# msp430g2553o.net
KiCad netlist of a schematic drawn in Altium Designer
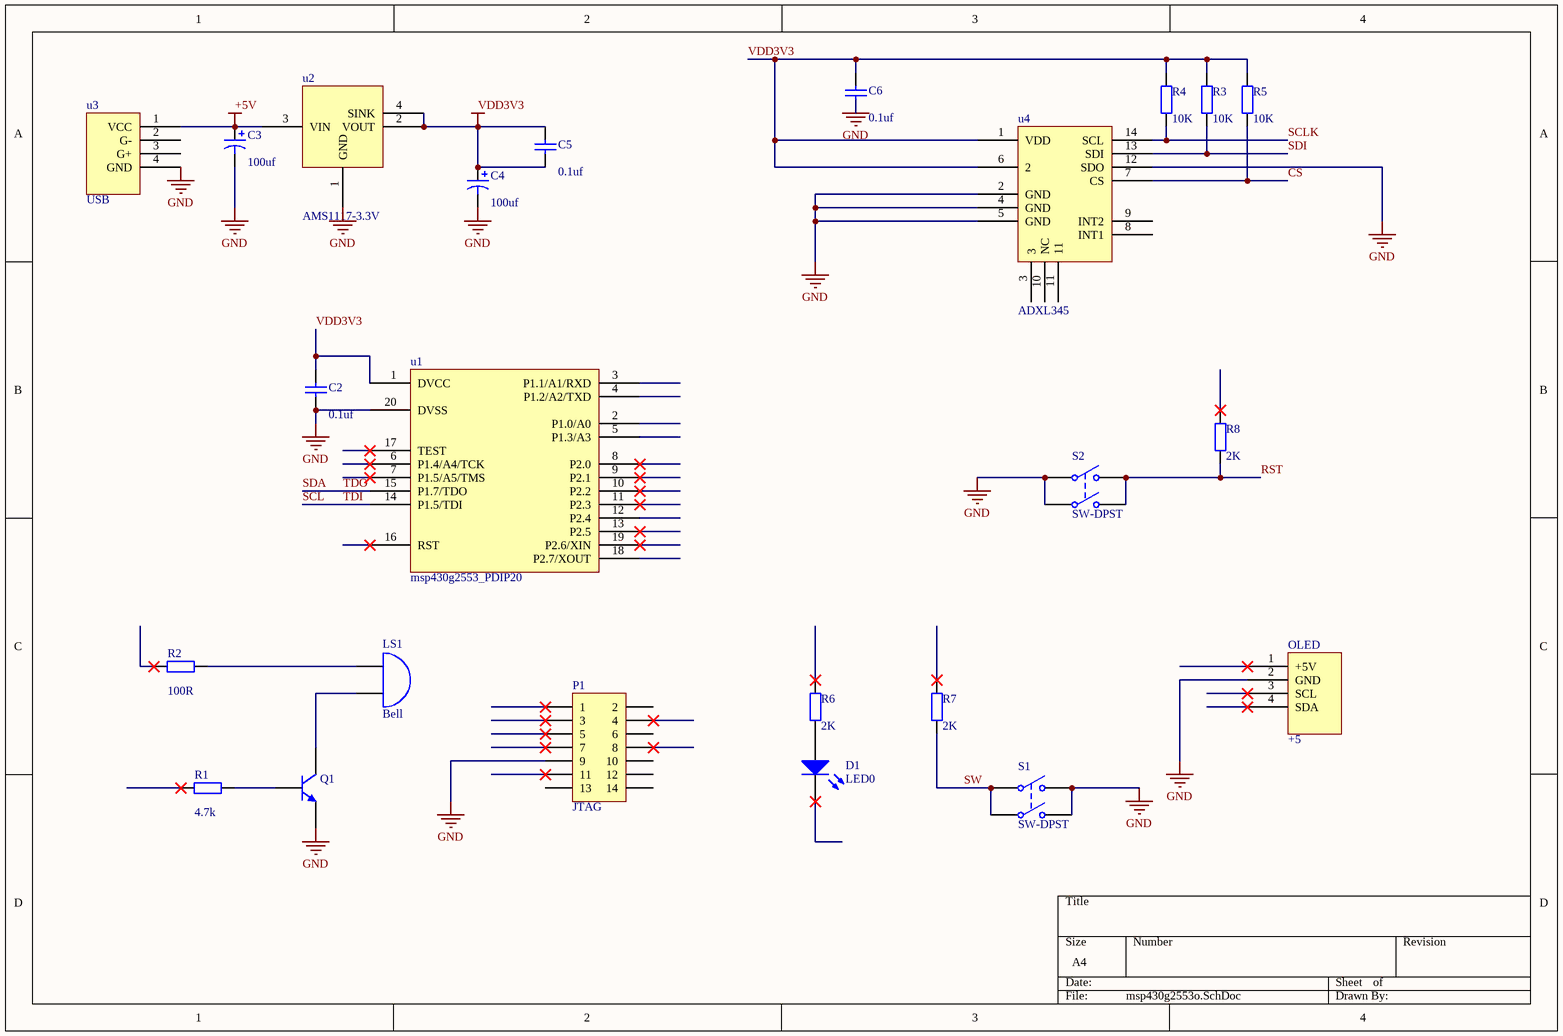
[diagram p0: msp430g2553o.SchDoc]

(export (version "E")
  (design (tool "Eeschema 10.0.6"))
  (components
    (comp (ref "C2")
      (value "0.1uf")
      (footprint "6-0805_N")
      (description "Capacitor")
      (fields (field (name "Comment") "Cap") (field (name "PUBLISHER") "Altium Limited"))
      (libsource (lib "msp430g2553") (part "Cap"))
    )
    (comp (ref "C3")
      (value "100uf")
      (footprint "Cap2_polar")
      (description "Polarized Capacitor (Axial)")
      (fields (field (name "Comment") "Cap Pol2") (field (name "PUBLISHER") "Altium Limited"))
      (libsource (lib "msp430g2553") (part "Cap Pol2"))
    )
    (comp (ref "C4")
      (value "100uf")
      (footprint "Cap2_polar")
      (description "Polarized Capacitor (Axial)")
      (fields (field (name "Comment") "Cap Pol2") (field (name "PUBLISHER") "Altium Limited"))
      (libsource (lib "msp430g2553") (part "Cap Pol2"))
    )
    (comp (ref "C5")
      (value "0.1uf")
      (footprint "6-0805_N")
      (description "Capacitor")
      (fields (field (name "Comment") "Cap") (field (name "PUBLISHER") "Altium Limited"))
      (libsource (lib "msp430g2553") (part "Cap"))
    )
    (comp (ref "C6")
      (value "0.1uf")
      (footprint "6-0805_N")
      (description "Capacitor")
      (fields (field (name "Comment") "Cap") (field (name "PUBLISHER") "Altium Limited"))
      (libsource (lib "msp430g2553") (part "Cap"))
    )
    (comp (ref "D1")
      (value "LED0")
      (footprint "6-0805_N - duplicate")
      (description "Typical INFRARED GaAs LED")
      (fields (field (name "PUBLISHER") "Altium Limited"))
      (libsource (lib "msp430g2553") (part "LED0"))
    )
    (comp (ref "LS1")
      (value "Bell")
      (footprint "bell")
      (description "Electrical Bell")
      (fields (field (name "PUBLISHER") "Altium Limited"))
      (libsource (lib "msp430g2553") (part "Bell"))
    )
    (comp (ref "OLED") (value "+5") (footprint "OLED") (libsource (lib "msp430g2553") (part "OLED")))
    (comp (ref "P1")
      (value "JTAG")
      (footprint "HDR2X7H")
      (description "Header, 7-Pin, Dual row")
      (fields (field (name "PUBLISHER") "Altium Limited"))
      (libsource (lib "msp430g2553") (part "JTAG"))
    )
    (comp (ref "Q1")
      (value "NPN")
      (footprint "SOT23_N")
      (description "NPN Bipolar Transistor")
      (fields (field (name "PUBLISHER") "Altium Limited"))
      (libsource (lib "msp430g2553") (part "NPN"))
    )
    (comp (ref "R1")
      (value "4.7k")
      (footprint "6-0805_N")
      (description "Resistor")
      (fields (field (name "Comment") "Res2") (field (name "PUBLISHER") "Altium Limited"))
      (libsource (lib "") (part "Res2_1"))
    )
    (comp (ref "R2")
      (value "100R")
      (footprint "6-0805_N")
      (description "Resistor")
      (fields (field (name "Comment") "Res2") (field (name "PUBLISHER") "Altium Limited"))
      (libsource (lib "") (part "Res2_1"))
    )
    (comp (ref "R3")
      (value "10K")
      (footprint "6-0805_N")
      (description "Resistor")
      (fields (field (name "Comment") "Res2") (field (name "PUBLISHER") "Altium Limited"))
      (libsource (lib "msp430g2553") (part "Res2"))
    )
    (comp (ref "R4")
      (value "10K")
      (footprint "6-0805_N")
      (description "Resistor")
      (fields (field (name "Comment") "Res2") (field (name "PUBLISHER") "Altium Limited"))
      (libsource (lib "msp430g2553") (part "Res2"))
    )
    (comp (ref "R5")
      (value "10K")
      (footprint "6-0805_N")
      (description "Resistor")
      (fields (field (name "Comment") "Res2") (field (name "PUBLISHER") "Altium Limited"))
      (libsource (lib "msp430g2553") (part "Res2"))
    )
    (comp (ref "R6")
      (value "2K")
      (footprint "6-0805_N")
      (description "Resistor")
      (fields (field (name "Comment") "Res2") (field (name "PUBLISHER") "Altium Limited"))
      (libsource (lib "msp430g2553") (part "Res2"))
    )
    (comp (ref "R7")
      (value "2K")
      (footprint "6-0805_N")
      (description "Resistor")
      (fields (field (name "Comment") "Res2") (field (name "PUBLISHER") "Altium Limited"))
      (libsource (lib "msp430g2553") (part "Res2"))
    )
    (comp (ref "R8")
      (value "2K")
      (footprint "6-0805_N")
      (description "Resistor")
      (fields (field (name "Comment") "Res2") (field (name "PUBLISHER") "Altium Limited"))
      (libsource (lib "msp430g2553") (part "Res2"))
    )
    (comp (ref "S1")
      (value "SW-DPST")
      (footprint "DPST-4")
      (description "Double-Pole, Single-Throw Switch")
      (fields (field (name "PUBLISHER") "Altium Limited"))
      (libsource (lib "msp430g2553") (part "SW-DPST"))
    )
    (comp (ref "S2")
      (value "SW-DPST")
      (footprint "DPST-4")
      (description "Double-Pole, Single-Throw Switch")
      (fields (field (name "PUBLISHER") "Altium Limited"))
      (libsource (lib "msp430g2553") (part "SW-DPST"))
    )
    (comp (ref "u1")
      (value "msp430g2553_PDIP20")
      (footprint "DIP20")
      (libsource (lib "msp430g2553") (part "msp430g2553_PDIP20"))
    )
    (comp (ref "u2")
      (value "AMS1117-3.3V")
      (footprint "SOT223_N")
      (libsource (lib "msp430g2553") (part "AMS1117-3.3V"))
    )
    (comp (ref "u3") (value "USB") (footprint "USB2.5-2H4") (libsource (lib "msp430g2553") (part "USB")))
    (comp (ref "u4") (value "ADXL345") (footprint "ADXL345") (libsource (lib "msp430g2553") (part "ADXL345")))
  )
  (nets
    (net (code "1") (name "+5") (class "Default")
      (node (ref "C3") (pin "2") (pinfunction "2_2") (pintype "passive"))
      (node (ref "u2") (pin "3") (pinfunction "VIN_3") (pintype "passive"))
      (node (ref "u3") (pin "1") (pinfunction "VCC_1") (pintype "passive"))
    )
    (net (code "3") (name "/CS") (class "Default")
      (node (ref "R5") (pin "1") (pinfunction "1_1") (pintype "passive"))
      (node (ref "u4") (pin "7") (pinfunction "CS_7") (pintype "passive"))
    )
    (net (code "4") (name "/RST") (class "Default")
      (node (ref "R8") (pin "1") (pinfunction "1_1") (pintype "passive"))
      (node (ref "S2") (pin "3") (pinfunction "NO1_3") (pintype "passive"))
      (node (ref "S2") (pin "4") (pinfunction "NO2_4") (pintype "passive"))
    )
    (net (code "5") (name "/SCL") (class "Default")
      (node (ref "u1") (pin "14") (pinfunction "P1.5/TDI_14") (pintype "passive"))
    )
    (net (code "6") (name "/SCLK") (class "Default")
      (node (ref "R4") (pin "1") (pinfunction "1_1") (pintype "passive"))
      (node (ref "u4") (pin "14") (pinfunction "SCL_14") (pintype "passive"))
    )
    (net (code "7") (name "/SDA") (class "Default")
      (node (ref "u1") (pin "15") (pinfunction "P1.7/TDO_15") (pintype "passive"))
    )
    (net (code "8") (name "/SDI") (class "Default")
      (node (ref "R3") (pin "1") (pinfunction "1_1") (pintype "passive"))
      (node (ref "u4") (pin "13") (pinfunction "SDI_13") (pintype "passive"))
    )
    (net (code "9") (name "/SW") (class "Default")
      (node (ref "R7") (pin "1") (pinfunction "1_1") (pintype "passive"))
      (node (ref "S1") (pin "1") (pinfunction "COMMON1_1") (pintype "passive"))
      (node (ref "S1") (pin "2") (pinfunction "COMMON2_2") (pintype "passive"))
    )
    (net (code "10") (name "/VDD3V3") (class "Default")
      (node (ref "C2") (pin "2") (pinfunction "2_2") (pintype "passive"))
      (node (ref "C6") (pin "2") (pinfunction "2_2") (pintype "passive"))
      (node (ref "R3") (pin "2") (pinfunction "2_2") (pintype "passive"))
      (node (ref "R4") (pin "2") (pinfunction "2_2") (pintype "passive"))
      (node (ref "R5") (pin "2") (pinfunction "2_2") (pintype "passive"))
      (node (ref "u1") (pin "1") (pinfunction "DVCC_1") (pintype "passive"))
      (node (ref "u4") (pin "1") (pinfunction "VDD_1") (pintype "passive"))
      (node (ref "u4") (pin "6") (pinfunction "2_6") (pintype "passive"))
    )
    (net (code "11") (name "3.3") (class "Default")
      (node (ref "C4") (pin "2") (pinfunction "2_2") (pintype "passive"))
      (node (ref "C5") (pin "1") (pinfunction "1_1") (pintype "passive"))
      (node (ref "C5") (pin "2") (pinfunction "2_2") (pintype "passive"))
      (node (ref "u2") (pin "2") (pinfunction "VOUT_2") (pintype "passive"))
      (node (ref "u2") (pin "4") (pinfunction "SINK_4") (pintype "passive"))
    )
    (net (code "12") (name "GND") (class "Default")
      (node (ref "C2") (pin "1") (pinfunction "1_1") (pintype "passive"))
      (node (ref "C3") (pin "1") (pinfunction "1_1") (pintype "passive"))
      (node (ref "C4") (pin "1") (pinfunction "1_1") (pintype "passive"))
      (node (ref "C6") (pin "1") (pinfunction "1_1") (pintype "passive"))
      (node (ref "OLED") (pin "2") (pinfunction "GND_2") (pintype "passive"))
      (node (ref "P1") (pin "9") (pinfunction "9_9") (pintype "passive"))
      (node (ref "Q1") (pin "3") (pinfunction "E_3") (pintype "passive"))
      (node (ref "S1") (pin "3") (pinfunction "NO1_3") (pintype "passive"))
      (node (ref "S1") (pin "4") (pinfunction "NO2_4") (pintype "passive"))
      (node (ref "S2") (pin "1") (pinfunction "COMMON1_1") (pintype "passive"))
      (node (ref "S2") (pin "2") (pinfunction "COMMON2_2") (pintype "passive"))
      (node (ref "u1") (pin "20") (pinfunction "DVSS_20") (pintype "passive"))
      (node (ref "u2") (pin "1") (pinfunction "GND_1") (pintype "passive"))
      (node (ref "u3") (pin "4") (pinfunction "GND_4") (pintype "passive"))
      (node (ref "u4") (pin "12") (pinfunction "SDO_12") (pintype "passive"))
      (node (ref "u4") (pin "2") (pinfunction "GND_2") (pintype "passive"))
      (node (ref "u4") (pin "4") (pinfunction "GND_4") (pintype "passive"))
      (node (ref "u4") (pin "5") (pinfunction "GND_5") (pintype "passive"))
    )
    (net (code "13") (name "Net-(D1-A)") (class "Default")
      (node (ref "D1") (pin "1") (pinfunction "A_1") (pintype "passive"))
      (node (ref "R6") (pin "1") (pinfunction "1_1") (pintype "passive"))
    )
    (net (code "14") (name "Net-(LS1-A)") (class "Default")
      (node (ref "LS1") (pin "1") (pinfunction "A_1") (pintype "passive"))
      (node (ref "R2") (pin "2") (pinfunction "2_2") (pintype "passive"))
    )
    (net (code "15") (name "Net-(LS1-B)") (class "Default")
      (node (ref "LS1") (pin "2") (pinfunction "B_2") (pintype "passive"))
      (node (ref "Q1") (pin "1") (pinfunction "C_1") (pintype "passive"))
    )
    (net (code "16") (name "Net-(Q1-B)") (class "Default")
      (node (ref "Q1") (pin "2") (pinfunction "B_2") (pintype "passive"))
      (node (ref "R1") (pin "2") (pinfunction "2_2") (pintype "passive"))
    )
    (net (code "17") (name "unconnected-(D1-K-Pad2)") (class "Default")
      (node (ref "D1") (pin "2") (pinfunction "K_2") (pintype "passive+no_connect"))
    )
    (net (code "18") (name "unconnected-(OLED-+5V-Pad1)") (class "Default")
      (node (ref "OLED") (pin "1") (pinfunction "+5V_1") (pintype "passive+no_connect"))
    )
    (net (code "19") (name "unconnected-(OLED-SCL-Pad3)") (class "Default")
      (node (ref "OLED") (pin "3") (pinfunction "SCL_3") (pintype "passive+no_connect"))
    )
    (net (code "20") (name "unconnected-(OLED-SDA-Pad4)") (class "Default")
      (node (ref "OLED") (pin "4") (pinfunction "SDA_4") (pintype "passive+no_connect"))
    )
    (net (code "21") (name "unconnected-(P1-Pad1)") (class "Default")
      (node (ref "P1") (pin "1") (pinfunction "1_1") (pintype "passive+no_connect"))
    )
    (net (code "22") (name "unconnected-(P1-Pad2)") (class "Default")
      (node (ref "P1") (pin "2") (pinfunction "2_2") (pintype "passive"))
    )
    (net (code "23") (name "unconnected-(P1-Pad3)") (class "Default")
      (node (ref "P1") (pin "3") (pinfunction "3_3") (pintype "passive+no_connect"))
    )
    (net (code "24") (name "unconnected-(P1-Pad4)") (class "Default")
      (node (ref "P1") (pin "4") (pinfunction "4_4") (pintype "passive+no_connect"))
    )
    (net (code "25") (name "unconnected-(P1-Pad5)") (class "Default")
      (node (ref "P1") (pin "5") (pinfunction "5_5") (pintype "passive+no_connect"))
    )
    (net (code "26") (name "unconnected-(P1-Pad6)") (class "Default")
      (node (ref "P1") (pin "6") (pinfunction "6_6") (pintype "passive"))
    )
    (net (code "27") (name "unconnected-(P1-Pad7)") (class "Default")
      (node (ref "P1") (pin "7") (pinfunction "7_7") (pintype "passive+no_connect"))
    )
    (net (code "28") (name "unconnected-(P1-Pad8)") (class "Default")
      (node (ref "P1") (pin "8") (pinfunction "8_8") (pintype "passive+no_connect"))
    )
    (net (code "29") (name "unconnected-(P1-Pad10)") (class "Default")
      (node (ref "P1") (pin "10") (pinfunction "10_10") (pintype "passive"))
    )
    (net (code "30") (name "unconnected-(P1-Pad11)") (class "Default")
      (node (ref "P1") (pin "11") (pinfunction "11_11") (pintype "passive+no_connect"))
    )
    (net (code "31") (name "unconnected-(P1-Pad12)") (class "Default")
      (node (ref "P1") (pin "12") (pinfunction "12_12") (pintype "passive"))
    )
    (net (code "32") (name "unconnected-(P1-Pad13)") (class "Default")
      (node (ref "P1") (pin "13") (pinfunction "13_13") (pintype "passive"))
    )
    (net (code "33") (name "unconnected-(P1-Pad14)") (class "Default")
      (node (ref "P1") (pin "14") (pinfunction "14_14") (pintype "passive"))
    )
    (net (code "34") (name "unconnected-(R1-Pad1)") (class "Default")
      (node (ref "R1") (pin "1") (pinfunction "1_1") (pintype "passive+no_connect"))
    )
    (net (code "35") (name "unconnected-(R2-Pad1)") (class "Default")
      (node (ref "R2") (pin "1") (pinfunction "1_1") (pintype "passive+no_connect"))
    )
    (net (code "36") (name "unconnected-(R6-Pad2)") (class "Default")
      (node (ref "R6") (pin "2") (pinfunction "2_2") (pintype "passive+no_connect"))
    )
    (net (code "37") (name "unconnected-(R7-Pad2)") (class "Default")
      (node (ref "R7") (pin "2") (pinfunction "2_2") (pintype "passive+no_connect"))
    )
    (net (code "38") (name "unconnected-(R8-Pad2)") (class "Default")
      (node (ref "R8") (pin "2") (pinfunction "2_2") (pintype "passive+no_connect"))
    )
    (net (code "39") (name "unconnected-(u1-P1.0{slash}A0-Pad2)") (class "Default")
      (node (ref "u1") (pin "2") (pinfunction "P1.0/A0_2") (pintype "passive"))
    )
    (net (code "40") (name "unconnected-(u1-P1.1{slash}A1{slash}RXD-Pad3)") (class "Default")
      (node (ref "u1") (pin "3") (pinfunction "P1.1/A1/RXD_3") (pintype "passive"))
    )
    (net (code "41") (name "unconnected-(u1-P1.2{slash}A2{slash}TXD-Pad4)") (class "Default")
      (node (ref "u1") (pin "4") (pinfunction "P1.2/A2/TXD_4") (pintype "passive"))
    )
    (net (code "42") (name "unconnected-(u1-P1.3{slash}A3-Pad5)") (class "Default")
      (node (ref "u1") (pin "5") (pinfunction "P1.3/A3_5") (pintype "passive"))
    )
    (net (code "43") (name "unconnected-(u1-P1.4{slash}A4{slash}TCK-Pad6)") (class "Default")
      (node (ref "u1") (pin "6") (pinfunction "P1.4/A4/TCK_6") (pintype "passive+no_connect"))
    )
    (net (code "44") (name "unconnected-(u1-P1.5{slash}A5{slash}TMS-Pad7)") (class "Default")
      (node (ref "u1") (pin "7") (pinfunction "P1.5/A5/TMS_7") (pintype "passive+no_connect"))
    )
    (net (code "45") (name "unconnected-(u1-P2.0-Pad8)") (class "Default")
      (node (ref "u1") (pin "8") (pinfunction "P2.0_8") (pintype "passive+no_connect"))
    )
    (net (code "46") (name "unconnected-(u1-P2.1-Pad9)") (class "Default")
      (node (ref "u1") (pin "9") (pinfunction "P2.1_9") (pintype "passive+no_connect"))
    )
    (net (code "47") (name "unconnected-(u1-P2.2-Pad10)") (class "Default")
      (node (ref "u1") (pin "10") (pinfunction "P2.2_10") (pintype "passive+no_connect"))
    )
    (net (code "48") (name "unconnected-(u1-P2.3-Pad11)") (class "Default")
      (node (ref "u1") (pin "11") (pinfunction "P2.3_11") (pintype "passive+no_connect"))
    )
    (net (code "49") (name "unconnected-(u1-P2.4-Pad12)") (class "Default")
      (node (ref "u1") (pin "12") (pinfunction "P2.4_12") (pintype "passive"))
    )
    (net (code "50") (name "unconnected-(u1-P2.5-Pad13)") (class "Default")
      (node (ref "u1") (pin "13") (pinfunction "P2.5_13") (pintype "passive+no_connect"))
    )
    (net (code "51") (name "unconnected-(u1-P2.6{slash}XIN-Pad19)") (class "Default")
      (node (ref "u1") (pin "19") (pinfunction "P2.6/XIN_19") (pintype "passive+no_connect"))
    )
    (net (code "52") (name "unconnected-(u1-P2.7{slash}XOUT-Pad18)") (class "Default")
      (node (ref "u1") (pin "18") (pinfunction "P2.7/XOUT_18") (pintype "passive"))
    )
    (net (code "53") (name "unconnected-(u1-RST-Pad16)") (class "Default")
      (node (ref "u1") (pin "16") (pinfunction "RST_16") (pintype "passive+no_connect"))
    )
    (net (code "54") (name "unconnected-(u1-TEST-Pad17)") (class "Default")
      (node (ref "u1") (pin "17") (pinfunction "TEST_17") (pintype "passive+no_connect"))
    )
    (net (code "55") (name "unconnected-(u3-G+-Pad3)") (class "Default")
      (node (ref "u3") (pin "3") (pinfunction "G+_3") (pintype "passive"))
    )
    (net (code "56") (name "unconnected-(u3-G--Pad2)") (class "Default")
      (node (ref "u3") (pin "2") (pinfunction "G-_2") (pintype "passive"))
    )
    (net (code "57") (name "unconnected-(u4-INT1-Pad8)") (class "Default")
      (node (ref "u4") (pin "8") (pinfunction "INT1_8") (pintype "passive"))
    )
    (net (code "58") (name "unconnected-(u4-INT2-Pad9)") (class "Default")
      (node (ref "u4") (pin "9") (pinfunction "INT2_9") (pintype "passive"))
    )
    (net (code "59") (name "unconnected-(u4-NC-Pad10)") (class "Default")
      (node (ref "u4") (pin "10") (pinfunction "NC_10") (pintype "passive"))
    )
    (net (code "60") (name "unconnected-(u4-Pad3)") (class "Default")
      (node (ref "u4") (pin "3") (pinfunction "3_3") (pintype "passive"))
    )
    (net (code "61") (name "unconnected-(u4-Pad11)") (class "Default")
      (node (ref "u4") (pin "11") (pinfunction "11_11") (pintype "passive"))
    )
  )
)
